# mux_chip_test_mk2.net
KiCad netlist of a schematic drawn in EAGLE
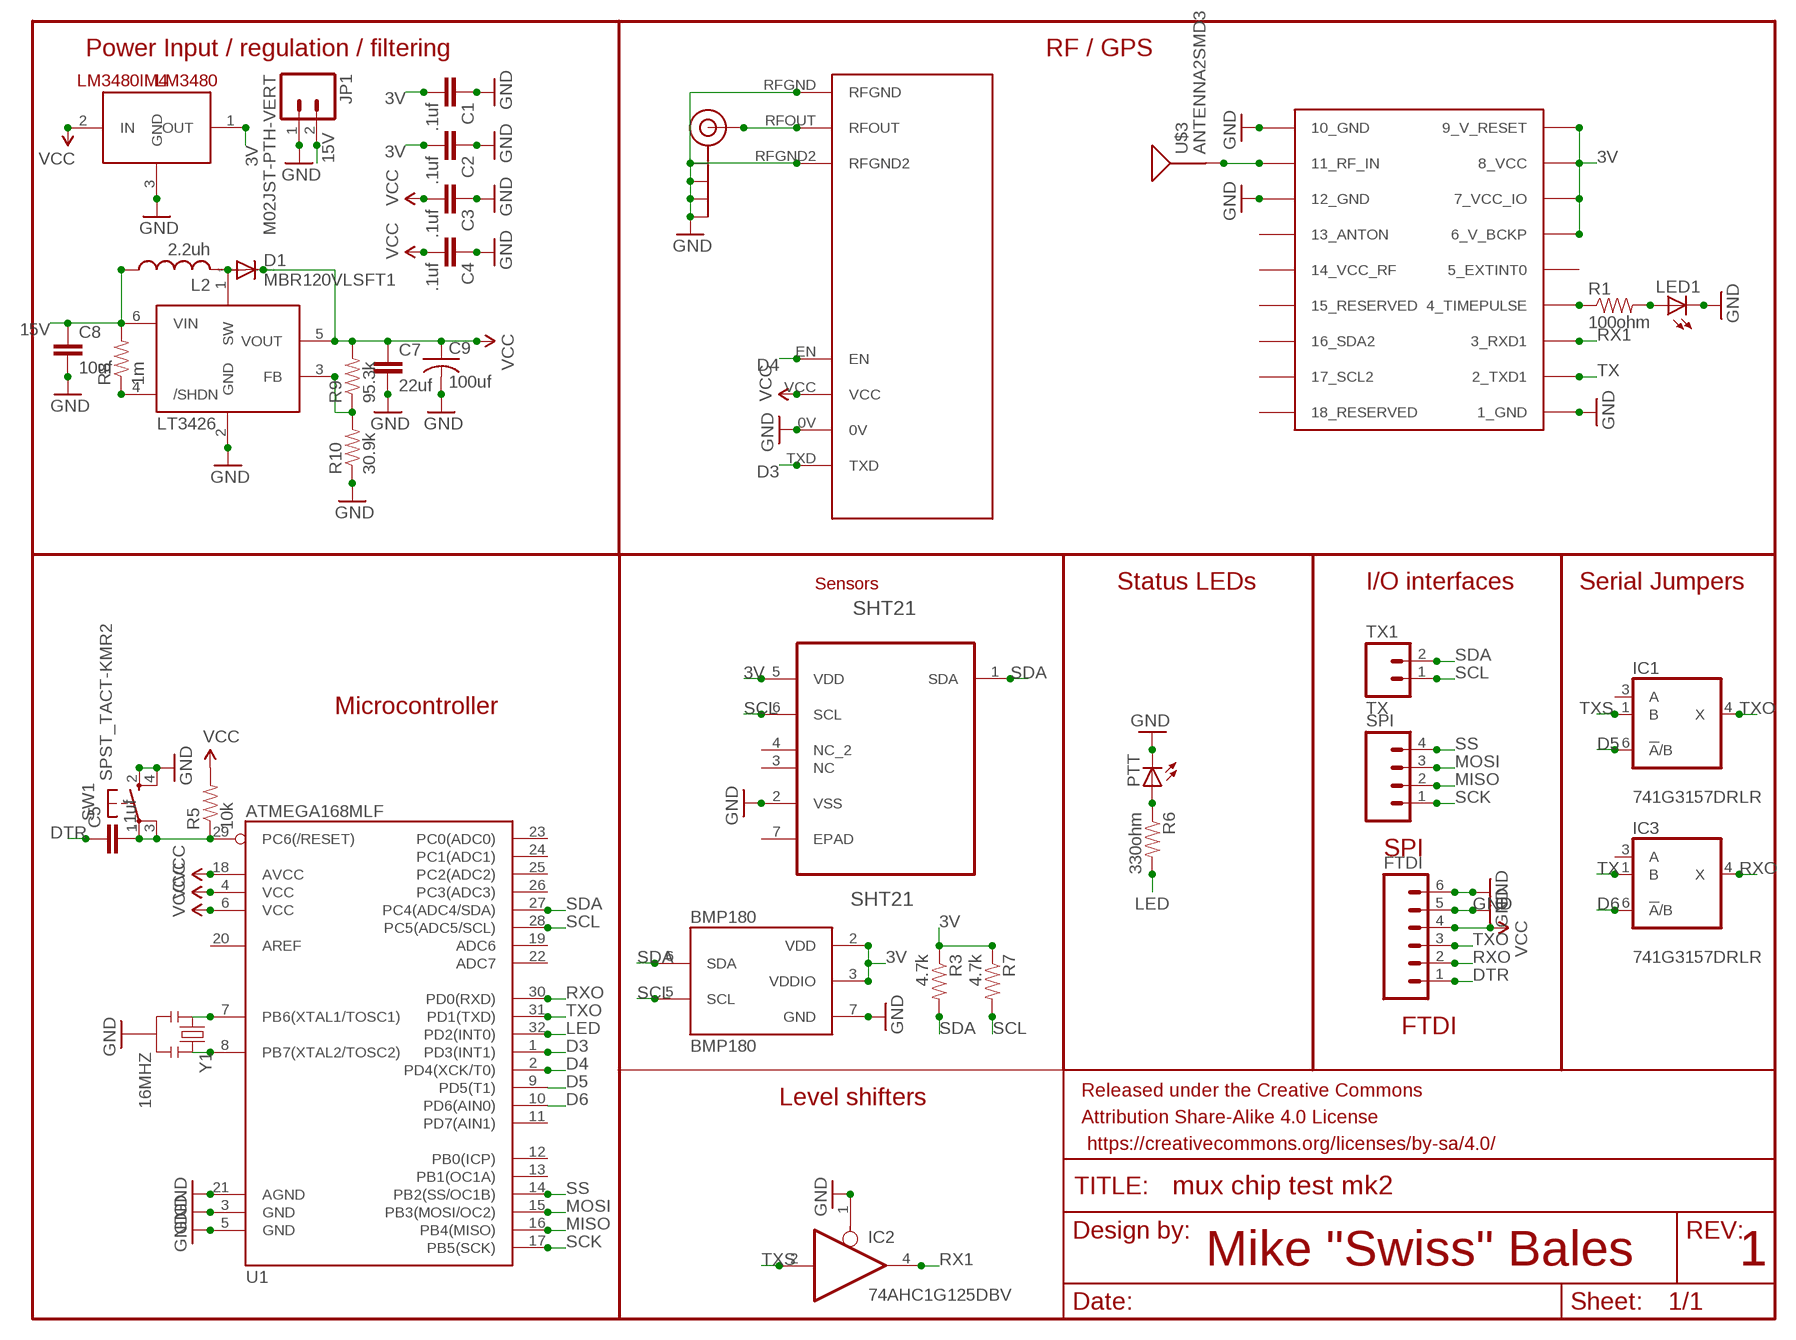
[diagram p0: schematic, sheet 1]

(export (version "E")
  (design (tool "Eeschema 10.0.6"))
  (components
    (comp (ref "BMP180")
      (value "BMP180")
      (footprint "eagle-import:BMP180")
      (libsource (lib "eagle-import") (part "BMP180"))
    )
    (comp (ref "C1")
      (value ".1uf")
      (footprint "eagle-import:0805")
      (libsource (lib "eagle-import") (part "CAP0805"))
    )
    (comp (ref "C2")
      (value ".1uf")
      (footprint "eagle-import:0805")
      (libsource (lib "eagle-import") (part "CAP0805"))
    )
    (comp (ref "C3")
      (value ".1uf")
      (footprint "eagle-import:0805")
      (libsource (lib "eagle-import") (part "CAP0805"))
    )
    (comp (ref "C4")
      (value ".1uf")
      (footprint "eagle-import:0805")
      (libsource (lib "eagle-import") (part "CAP0805"))
    )
    (comp (ref "C5")
      (value ".1uf")
      (footprint "eagle-import:0805")
      (libsource (lib "eagle-import") (part "CAP0805"))
    )
    (comp (ref "C7")
      (value "22uf")
      (footprint "eagle-import:0805")
      (libsource (lib "eagle-import") (part "CAP0805"))
    )
    (comp (ref "C8")
      (value "10uf")
      (footprint "eagle-import:0805")
      (libsource (lib "eagle-import") (part "CAP0805"))
    )
    (comp (ref "C9")
      (value "100uf")
      (footprint "eagle-import:C1206")
      (libsource (lib "eagle-import") (part "C-USC1206"))
    )
    (comp (ref "D1")
      (value "MBR120VLSFT1")
      (footprint "eagle-import:SOD123")
      (libsource (lib "eagle-import") (part "DIODE-SOD123"))
    )
    (comp (ref "FRAME1")
      (value "FRAME-LETTER")
      (footprint "eagle-import:CREATIVE_COMMONS")
      (libsource (lib "eagle-import") (part "FRAME-LETTER"))
    )
    (comp (ref "FTDI")
      (value "M06NO_SILK_FEMALE_PTH")
      (footprint "eagle-import:1X06_NO_SILK")
      (libsource (lib "eagle-import") (part "M06NO_SILK_FEMALE_PTH"))
    )
    (comp (ref "IC1")
      (value "741G3157DRLR")
      (footprint "eagle-import:DRL_R-PDSO-N6")
      (libsource (lib "eagle-import") (part "741G3157DRLR"))
    )
    (comp (ref "IC2")
      (value "74AHC1G125DBV")
      (footprint "eagle-import:SOT23-5")
      (libsource (lib "eagle-import") (part "741G125DBVAHC"))
    )
    (comp (ref "IC3")
      (value "741G3157DRLR")
      (footprint "eagle-import:DRL_R-PDSO-N6")
      (libsource (lib "eagle-import") (part "741G3157DRLR"))
    )
    (comp (ref "J$1")
      (value "SMA_EDGE")
      (footprint "eagle-import:SMA-EDGE")
      (libsource (lib "eagle-import") (part "SMA_EDGE"))
    )
    (comp (ref "JP1")
      (value "M02JST-PTH-VERT")
      (footprint "eagle-import:JST-2-PTH-VERT")
      (libsource (lib "eagle-import") (part "M02JST-PTH-VERT"))
    )
    (comp (ref "L2")
      (value "2.2uh")
      (footprint "eagle-import:L1812")
      (libsource (lib "eagle-import") (part "L-USL1812"))
    )
    (comp (ref "LED1")
      (value "LEDCHIP-LED0805")
      (footprint "eagle-import:CHIP-LED0805")
      (libsource (lib "eagle-import") (part "LEDCHIP-LED0805"))
    )
    (comp (ref "LM3480")
      (value "LM3480IM4")
      (footprint "eagle-import:SOT23-3")
      (libsource (lib "eagle-import") (part "LM3480IM4"))
    )
    (comp (ref "LT3426")
      (value "LT3426")
      (footprint "eagle-import:SOT23-6")
      (libsource (lib "eagle-import") (part "LT3426"))
    )
    (comp (ref "PTT")
      (value "LEDCHIP-LED0805")
      (footprint "eagle-import:CHIP-LED0805")
      (libsource (lib "eagle-import") (part "LEDCHIP-LED0805"))
    )
    (comp (ref "R1")
      (value "100ohm")
      (footprint "eagle-import:0805")
      (libsource (lib "eagle-import") (part "RESISTOR0805-RES"))
    )
    (comp (ref "R3")
      (value "4.7k")
      (footprint "eagle-import:0805")
      (libsource (lib "eagle-import") (part "RESISTOR0805-RES"))
    )
    (comp (ref "R5")
      (value "10k")
      (footprint "eagle-import:0805")
      (libsource (lib "eagle-import") (part "RESISTOR0805-RES"))
    )
    (comp (ref "R6")
      (value "330ohm")
      (footprint "eagle-import:0805")
      (libsource (lib "eagle-import") (part "RESISTOR0805-RES"))
    )
    (comp (ref "R7")
      (value "4.7k")
      (footprint "eagle-import:0805")
      (libsource (lib "eagle-import") (part "RESISTOR0805-RES"))
    )
    (comp (ref "R8")
      (value "1m")
      (footprint "eagle-import:0805")
      (libsource (lib "eagle-import") (part "RESISTOR0805-RES"))
    )
    (comp (ref "R9")
      (value "95.3k")
      (footprint "eagle-import:0805")
      (libsource (lib "eagle-import") (part "RESISTOR0805-RES"))
    )
    (comp (ref "R10")
      (value "30.9k")
      (footprint "eagle-import:0805")
      (libsource (lib "eagle-import") (part "RESISTOR0805-RES"))
    )
    (comp (ref "SHT21")
      (value "SHT21")
      (footprint "eagle-import:DFN300X300X110-7N")
      (libsource (lib "eagle-import") (part "SHT21"))
    )
    (comp (ref "SPI")
      (value "M04JST-PTH-VERT")
      (footprint "eagle-import:JST-4-PTH-VERT")
      (libsource (lib "eagle-import") (part "M04JST-PTH-VERT"))
    )
    (comp (ref "SW1")
      (value "SPST_TACT-KMR2")
      (footprint "eagle-import:KMR2")
      (libsource (lib "eagle-import") (part "SPST_TACT-KMR2"))
    )
    (comp (ref "TX1")
      (value "TX")
      (footprint "eagle-import:JST-2-PTH-VERT")
      (libsource (lib "eagle-import") (part "M02JST-PTH-VERT"))
    )
    (comp (ref "U$1")
      (value "UBLOX_MAX")
      (footprint "eagle-import:UBLOX_MAX")
      (libsource (lib "eagle-import") (part "UBLOX_MAX"))
    )
    (comp (ref "U$2")
      (value "RADIOMETRIX-HX1")
      (footprint "eagle-import:RADIOMETRIX-HX1")
      (libsource (lib "eagle-import") (part "RADIOMETRIX-HX1"))
    )
    (comp (ref "U$3")
      (value "ANTENNA2SMD3")
      (footprint "eagle-import:ANTENNA-CHIP4")
      (libsource (lib "eagle-import") (part "ANTENNA2SMD3"))
    )
    (comp (ref "U1")
      (value "ATMEGA168MLF")
      (footprint "eagle-import:MLF32")
      (libsource (lib "eagle-import") (part "ATMEGA168MLF"))
    )
    (comp (ref "Y1")
      (value "16MHZ")
      (footprint "eagle-import:RESONATOR-SMD")
      (libsource (lib "eagle-import") (part "RESONATOR16MHZ"))
    )
  )
  (nets
    (net (code "1") (name "/3V") (class "Default")
      (node (ref "BMP180") (pin "2") (pinfunction "VDD_2") (pintype "power_in"))
      (node (ref "BMP180") (pin "3") (pinfunction "VDDIO_3") (pintype "power_in"))
      (node (ref "C1") (pin "2") (pinfunction "2_2") (pintype "passive"))
      (node (ref "C2") (pin "2") (pinfunction "2_2") (pintype "passive"))
      (node (ref "LM3480") (pin "1") (pinfunction "OUT_1") (pintype "bidirectional"))
      (node (ref "R3") (pin "1") (pinfunction "1_1") (pintype "passive"))
      (node (ref "R7") (pin "1") (pinfunction "1_1") (pintype "passive"))
      (node (ref "SHT21") (pin "5") (pinfunction "VDD_5") (pintype "power_in"))
      (node (ref "U$1") (pin "6_V_BCKP") (pinfunction "6_V_BCKP_6_V_BCKP") (pintype "bidirectional"))
      (node (ref "U$1") (pin "7_VCC_IO") (pinfunction "7_VCC_IO_7_VCC_IO") (pintype "power_in"))
      (node (ref "U$1") (pin "8_VCC") (pinfunction "8_VCC_8_VCC") (pintype "power_in"))
      (node (ref "U$1") (pin "9_V_RESET") (pinfunction "9_V_RESET_9_V_RESET") (pintype "power_in"))
    )
    (net (code "2") (name "/15V") (class "Default")
      (node (ref "C8") (pin "1") (pinfunction "1_1") (pintype "passive"))
      (node (ref "JP1") (pin "2") (pinfunction "2_2") (pintype "passive"))
      (node (ref "L2") (pin "1") (pinfunction "1_1") (pintype "passive"))
      (node (ref "LT3426") (pin "6") (pinfunction "VIN_6") (pintype "input"))
      (node (ref "R8") (pin "2") (pinfunction "2_2") (pintype "passive"))
    )
    (net (code "3") (name "/D3") (class "Default")
      (node (ref "U$2") (pin "TXD") (pinfunction "TXD_TXD") (pintype "bidirectional"))
      (node (ref "U1") (pin "1") (pinfunction "PD3(INT1)_1") (pintype "bidirectional"))
    )
    (net (code "4") (name "/D4") (class "Default")
      (node (ref "U$2") (pin "EN") (pinfunction "EN_EN") (pintype "bidirectional"))
      (node (ref "U1") (pin "2") (pinfunction "PD4(XCK/T0)_2") (pintype "bidirectional"))
    )
    (net (code "5") (name "/D5") (class "Default")
      (node (ref "IC1") (pin "6") (pinfunction "~{A}/B_6") (pintype "input"))
      (node (ref "U1") (pin "9") (pinfunction "PD5(T1)_9") (pintype "bidirectional"))
    )
    (net (code "6") (name "/D6") (class "Default")
      (node (ref "IC3") (pin "6") (pinfunction "~{A}/B_6") (pintype "input"))
      (node (ref "U1") (pin "10") (pinfunction "PD6(AIN0)_10") (pintype "bidirectional"))
    )
    (net (code "7") (name "/DTR") (class "Default")
      (node (ref "C5") (pin "1") (pinfunction "1_1") (pintype "passive"))
      (node (ref "FTDI") (pin "1") (pinfunction "1_1") (pintype "passive"))
    )
    (net (code "8") (name "/LED") (class "Default")
      (node (ref "R6") (pin "2") (pinfunction "2_2") (pintype "passive"))
      (node (ref "U1") (pin "32") (pinfunction "PD2(INT0)_32") (pintype "bidirectional"))
    )
    (net (code "9") (name "/MISO") (class "Default")
      (node (ref "SPI") (pin "2") (pinfunction "2_2") (pintype "passive"))
      (node (ref "U1") (pin "16") (pinfunction "PB4(MISO)_16") (pintype "bidirectional"))
    )
    (net (code "10") (name "/MOSI") (class "Default")
      (node (ref "SPI") (pin "3") (pinfunction "3_3") (pintype "passive"))
      (node (ref "U1") (pin "15") (pinfunction "PB3(MOSI/OC2)_15") (pintype "bidirectional"))
    )
    (net (code "11") (name "/RX1") (class "Default")
      (node (ref "IC2") (pin "4") (pinfunction "O_4") (pintype "tri_state"))
      (node (ref "U$1") (pin "3_RXD1") (pinfunction "3_RXD1_3_RXD1") (pintype "bidirectional"))
    )
    (net (code "12") (name "/RXO") (class "Default")
      (node (ref "FTDI") (pin "2") (pinfunction "2_2") (pintype "passive"))
      (node (ref "IC3") (pin "4") (pinfunction "X_4") (pintype "bidirectional"))
      (node (ref "U1") (pin "30") (pinfunction "PD0(RXD)_30") (pintype "bidirectional"))
    )
    (net (code "13") (name "/SCK") (class "Default")
      (node (ref "SPI") (pin "1") (pinfunction "1_1") (pintype "passive"))
      (node (ref "U1") (pin "17") (pinfunction "PB5(SCK)_17") (pintype "bidirectional"))
    )
    (net (code "14") (name "/SCL") (class "Default")
      (node (ref "BMP180") (pin "5") (pinfunction "SCL_5") (pintype "input"))
      (node (ref "R7") (pin "2") (pinfunction "2_2") (pintype "passive"))
      (node (ref "SHT21") (pin "6") (pinfunction "SCL_6") (pintype "input"))
      (node (ref "TX1") (pin "1") (pinfunction "1_1") (pintype "passive"))
      (node (ref "U1") (pin "28") (pinfunction "PC5(ADC5/SCL)_28") (pintype "bidirectional"))
    )
    (net (code "15") (name "/SDA") (class "Default")
      (node (ref "BMP180") (pin "6") (pinfunction "SDA_6") (pintype "bidirectional"))
      (node (ref "R3") (pin "2") (pinfunction "2_2") (pintype "passive"))
      (node (ref "SHT21") (pin "1") (pinfunction "SDA_1") (pintype "bidirectional"))
      (node (ref "TX1") (pin "2") (pinfunction "2_2") (pintype "passive"))
      (node (ref "U1") (pin "27") (pinfunction "PC4(ADC4/SDA)_27") (pintype "bidirectional"))
    )
    (net (code "16") (name "/SS") (class "Default")
      (node (ref "SPI") (pin "4") (pinfunction "4_4") (pintype "passive"))
      (node (ref "U1") (pin "14") (pinfunction "PB2(SS/OC1B)_14") (pintype "bidirectional"))
    )
    (net (code "17") (name "/TX") (class "Default")
      (node (ref "IC3") (pin "1") (pinfunction "B_1") (pintype "bidirectional"))
      (node (ref "U$1") (pin "2_TXD1") (pinfunction "2_TXD1_2_TXD1") (pintype "bidirectional"))
    )
    (net (code "18") (name "/TXO") (class "Default")
      (node (ref "FTDI") (pin "3") (pinfunction "3_3") (pintype "passive"))
      (node (ref "IC1") (pin "4") (pinfunction "X_4") (pintype "bidirectional"))
      (node (ref "U1") (pin "31") (pinfunction "PD1(TXD)_31") (pintype "bidirectional"))
    )
    (net (code "19") (name "/TXS") (class "Default")
      (node (ref "IC1") (pin "1") (pinfunction "B_1") (pintype "bidirectional"))
      (node (ref "IC2") (pin "2") (pinfunction "I_2") (pintype "input"))
    )
    (net (code "20") (name "GND") (class "Default")
      (node (ref "BMP180") (pin "7") (pinfunction "GND_7") (pintype "power_in"))
      (node (ref "C1") (pin "1") (pinfunction "1_1") (pintype "passive"))
      (node (ref "C2") (pin "1") (pinfunction "1_1") (pintype "passive"))
      (node (ref "C3") (pin "1") (pinfunction "1_1") (pintype "passive"))
      (node (ref "C4") (pin "1") (pinfunction "1_1") (pintype "passive"))
      (node (ref "C7") (pin "2") (pinfunction "2_2") (pintype "passive"))
      (node (ref "C8") (pin "2") (pinfunction "2_2") (pintype "passive"))
      (node (ref "C9") (pin "2") (pinfunction "2_2") (pintype "passive"))
      (node (ref "FTDI") (pin "5") (pinfunction "5_5") (pintype "passive"))
      (node (ref "FTDI") (pin "6") (pinfunction "6_6") (pintype "passive"))
      (node (ref "IC2") (pin "1") (pinfunction "OE_1") (pintype "input"))
      (node (ref "J$1") (pin "GND@0") (pinfunction "GND_GND@0") (pintype "bidirectional"))
      (node (ref "J$1") (pin "GND@1") (pinfunction "GND_GND@1") (pintype "bidirectional"))
      (node (ref "J$1") (pin "GND@2") (pinfunction "GND_GND@2") (pintype "bidirectional"))
      (node (ref "J$1") (pin "GND@3") (pinfunction "GND_GND@3") (pintype "bidirectional"))
      (node (ref "JP1") (pin "1") (pinfunction "1_1") (pintype "passive"))
      (node (ref "LED1") (pin "C") (pinfunction "C_C") (pintype "passive"))
      (node (ref "LM3480") (pin "3") (pinfunction "GND_3") (pintype "bidirectional"))
      (node (ref "LT3426") (pin "2") (pinfunction "GND_2") (pintype "power_in"))
      (node (ref "PTT") (pin "C") (pinfunction "C_C") (pintype "passive"))
      (node (ref "R10") (pin "1") (pinfunction "1_1") (pintype "passive"))
      (node (ref "SHT21") (pin "2") (pinfunction "VSS_2") (pintype "power_in"))
      (node (ref "SW1") (pin "2") (pinfunction "S_2") (pintype "passive"))
      (node (ref "SW1") (pin "4") (pinfunction "S1_4") (pintype "passive"))
      (node (ref "U$1") (pin "10_GND") (pinfunction "10_GND_10_GND") (pintype "power_in"))
      (node (ref "U$1") (pin "12_GND") (pinfunction "12_GND_12_GND") (pintype "power_in"))
      (node (ref "U$1") (pin "1_GND") (pinfunction "1_GND_1_GND") (pintype "power_in"))
      (node (ref "U$2") (pin "0V") (pinfunction "0V_0V") (pintype "bidirectional"))
      (node (ref "U$2") (pin "RFGND") (pinfunction "RFGND_RFGND") (pintype "bidirectional"))
      (node (ref "U$2") (pin "RFGND2") (pinfunction "RFGND2_RFGND2") (pintype "bidirectional"))
      (node (ref "U1") (pin "21") (pinfunction "AGND_21") (pintype "bidirectional"))
      (node (ref "U1") (pin "3") (pinfunction "GND_3") (pintype "bidirectional"))
      (node (ref "U1") (pin "5") (pinfunction "GND_5") (pintype "bidirectional"))
      (node (ref "Y1") (pin "2") (pinfunction "2_2") (pintype "passive"))
    )
    (net (code "21") (name "Net-(J$1-SIGNAL)") (class "Default")
      (node (ref "J$1") (pin "SIG") (pinfunction "SIGNAL_SIG") (pintype "bidirectional"))
      (node (ref "U$2") (pin "RFOUT") (pinfunction "RFOUT_RFOUT") (pintype "bidirectional"))
    )
    (net (code "22") (name "Net-(LED1-PadA)") (class "Default")
      (node (ref "LED1") (pin "A") (pinfunction "A_A") (pintype "passive"))
      (node (ref "R1") (pin "2") (pinfunction "2_2") (pintype "passive"))
    )
    (net (code "23") (name "Net-(LT3426-FB)") (class "Default")
      (node (ref "LT3426") (pin "3") (pinfunction "FB_3") (pintype "input"))
      (node (ref "R10") (pin "2") (pinfunction "2_2") (pintype "passive"))
      (node (ref "R9") (pin "1") (pinfunction "1_1") (pintype "passive"))
    )
    (net (code "24") (name "Net-(LT3426-SW)") (class "Default")
      (node (ref "D1") (pin "A") (pinfunction "A_A") (pintype "passive"))
      (node (ref "L2") (pin "2") (pinfunction "2_2") (pintype "passive"))
      (node (ref "LT3426") (pin "1") (pinfunction "SW_1") (pintype "output"))
    )
    (net (code "25") (name "Net-(LT3426-{slash}SHDN)") (class "Default")
      (node (ref "LT3426") (pin "4") (pinfunction "/SHDN_4") (pintype "input"))
      (node (ref "R8") (pin "1") (pinfunction "1_1") (pintype "passive"))
    )
    (net (code "26") (name "Net-(PTT-PadA)") (class "Default")
      (node (ref "PTT") (pin "A") (pinfunction "A_A") (pintype "passive"))
      (node (ref "R6") (pin "1") (pinfunction "1_1") (pintype "passive"))
    )
    (net (code "27") (name "Net-(R1-Pad1)") (class "Default")
      (node (ref "R1") (pin "1") (pinfunction "1_1") (pintype "passive"))
      (node (ref "U$1") (pin "4_TIMEPULSE") (pinfunction "4_TIMEPULSE_4_TIMEPULSE") (pintype "bidirectional"))
    )
    (net (code "28") (name "Net-(SW1-P)") (class "Default")
      (node (ref "C5") (pin "2") (pinfunction "2_2") (pintype "passive"))
      (node (ref "R5") (pin "1") (pinfunction "1_1") (pintype "passive"))
      (node (ref "SW1") (pin "1") (pinfunction "P_1") (pintype "passive"))
      (node (ref "SW1") (pin "3") (pinfunction "P1_3") (pintype "passive"))
      (node (ref "U1") (pin "29") (pinfunction "PC6(/RESET)_29") (pintype "bidirectional"))
    )
    (net (code "29") (name "Net-(U$3-SIGNAL)") (class "Default")
      (node (ref "U$1") (pin "11_RF_IN") (pinfunction "11_RF_IN_11_RF_IN") (pintype "bidirectional"))
      (node (ref "U$3") (pin "SIG") (pinfunction "SIGNAL_SIG") (pintype "bidirectional"))
    )
    (net (code "30") (name "Net-(U1-PB6(XTAL1{slash}TOSC1))") (class "Default")
      (node (ref "U1") (pin "7") (pinfunction "PB6(XTAL1/TOSC1)_7") (pintype "bidirectional"))
      (node (ref "Y1") (pin "1") (pinfunction "1_1") (pintype "passive"))
    )
    (net (code "31") (name "Net-(U1-PB7(XTAL2{slash}TOSC2))") (class "Default")
      (node (ref "U1") (pin "8") (pinfunction "PB7(XTAL2/TOSC2)_8") (pintype "bidirectional"))
      (node (ref "Y1") (pin "3") (pinfunction "3_3") (pintype "passive"))
    )
    (net (code "32") (name "VCC") (class "Default")
      (node (ref "C3") (pin "2") (pinfunction "2_2") (pintype "passive"))
      (node (ref "C4") (pin "2") (pinfunction "2_2") (pintype "passive"))
      (node (ref "C7") (pin "1") (pinfunction "1_1") (pintype "passive"))
      (node (ref "C9") (pin "1") (pinfunction "1_1") (pintype "passive"))
      (node (ref "D1") (pin "C") (pinfunction "C_C") (pintype "passive"))
      (node (ref "FTDI") (pin "4") (pinfunction "4_4") (pintype "passive"))
      (node (ref "LM3480") (pin "2") (pinfunction "IN_2") (pintype "bidirectional"))
      (node (ref "LT3426") (pin "5") (pinfunction "VOUT_5") (pintype "output"))
      (node (ref "R5") (pin "2") (pinfunction "2_2") (pintype "passive"))
      (node (ref "R9") (pin "2") (pinfunction "2_2") (pintype "passive"))
      (node (ref "U$2") (pin "VCC") (pinfunction "VCC_VCC") (pintype "bidirectional"))
      (node (ref "U1") (pin "18") (pinfunction "AVCC_18") (pintype "bidirectional"))
      (node (ref "U1") (pin "4") (pinfunction "VCC_4") (pintype "bidirectional"))
      (node (ref "U1") (pin "6") (pinfunction "VCC_6") (pintype "bidirectional"))
    )
    (net (code "33") (name "unconnected-(IC1A-A-Pad3)") (class "Default")
      (node (ref "IC1") (pin "3") (pinfunction "A_3") (pintype "bidirectional"))
    )
    (net (code "34") (name "unconnected-(IC3A-A-Pad3)") (class "Default")
      (node (ref "IC3") (pin "3") (pinfunction "A_3") (pintype "bidirectional"))
    )
    (net (code "35") (name "unconnected-(SHT21-EPAD-Pad7)") (class "Default")
      (node (ref "SHT21") (pin "7") (pinfunction "EPAD_7") (pintype "passive"))
    )
    (net (code "36") (name "unconnected-(SHT21-NC-Pad3)") (class "Default")
      (node (ref "SHT21") (pin "3") (pinfunction "NC_3") (pintype "no_connect"))
    )
    (net (code "37") (name "unconnected-(SHT21-NC_2-Pad4)") (class "Default")
      (node (ref "SHT21") (pin "4") (pinfunction "NC_2_4") (pintype "no_connect"))
    )
    (net (code "38") (name "unconnected-(U$1-Pad5_EXTINT0)") (class "Default")
      (node (ref "U$1") (pin "5_EXTINT0") (pinfunction "5_EXTINT0_5_EXTINT0") (pintype "bidirectional"))
    )
    (net (code "39") (name "unconnected-(U$1-Pad13_ANTON)") (class "Default")
      (node (ref "U$1") (pin "13_ANTON") (pinfunction "13_ANTON_13_ANTON") (pintype "bidirectional"))
    )
    (net (code "40") (name "unconnected-(U$1-Pad14_VCC_RF)") (class "Default")
      (node (ref "U$1") (pin "14_VCC_RF") (pinfunction "14_VCC_RF_14_VCC_RF") (pintype "bidirectional"))
    )
    (net (code "41") (name "unconnected-(U$1-Pad15_RESERVED)") (class "Default")
      (node (ref "U$1") (pin "15_RESERVED") (pinfunction "15_RESERVED_15_RESERVED") (pintype "bidirectional"))
    )
    (net (code "42") (name "unconnected-(U$1-Pad16_SDA2)") (class "Default")
      (node (ref "U$1") (pin "16_SDA2") (pinfunction "16_SDA2_16_SDA2") (pintype "bidirectional"))
    )
    (net (code "43") (name "unconnected-(U$1-Pad17_SCL2)") (class "Default")
      (node (ref "U$1") (pin "17_SCL2") (pinfunction "17_SCL2_17_SCL2") (pintype "bidirectional"))
    )
    (net (code "44") (name "unconnected-(U$1-Pad18_RESERVED)") (class "Default")
      (node (ref "U$1") (pin "18_RESERVED") (pinfunction "18_RESERVED_18_RESERVED") (pintype "bidirectional"))
    )
    (net (code "45") (name "unconnected-(U1-ADC6-Pad19)") (class "Default")
      (node (ref "U1") (pin "19") (pinfunction "ADC6_19") (pintype "bidirectional"))
    )
    (net (code "46") (name "unconnected-(U1-ADC7-Pad22)") (class "Default")
      (node (ref "U1") (pin "22") (pinfunction "ADC7_22") (pintype "bidirectional"))
    )
    (net (code "47") (name "unconnected-(U1-AREF-Pad20)") (class "Default")
      (node (ref "U1") (pin "20") (pinfunction "AREF_20") (pintype "bidirectional"))
    )
    (net (code "48") (name "unconnected-(U1-PB0(ICP)-Pad12)") (class "Default")
      (node (ref "U1") (pin "12") (pinfunction "PB0(ICP)_12") (pintype "bidirectional"))
    )
    (net (code "49") (name "unconnected-(U1-PB1(OC1A)-Pad13)") (class "Default")
      (node (ref "U1") (pin "13") (pinfunction "PB1(OC1A)_13") (pintype "bidirectional"))
    )
    (net (code "50") (name "unconnected-(U1-PC0(ADC0)-Pad23)") (class "Default")
      (node (ref "U1") (pin "23") (pinfunction "PC0(ADC0)_23") (pintype "bidirectional"))
    )
    (net (code "51") (name "unconnected-(U1-PC1(ADC1)-Pad24)") (class "Default")
      (node (ref "U1") (pin "24") (pinfunction "PC1(ADC1)_24") (pintype "bidirectional"))
    )
    (net (code "52") (name "unconnected-(U1-PC2(ADC2)-Pad25)") (class "Default")
      (node (ref "U1") (pin "25") (pinfunction "PC2(ADC2)_25") (pintype "bidirectional"))
    )
    (net (code "53") (name "unconnected-(U1-PC3(ADC3)-Pad26)") (class "Default")
      (node (ref "U1") (pin "26") (pinfunction "PC3(ADC3)_26") (pintype "bidirectional"))
    )
    (net (code "54") (name "unconnected-(U1-PD7(AIN1)-Pad11)") (class "Default")
      (node (ref "U1") (pin "11") (pinfunction "PD7(AIN1)_11") (pintype "bidirectional"))
    )
  )
)
